# Peripherals.net
KiCad netlist of a schematic drawn in Altium Designer
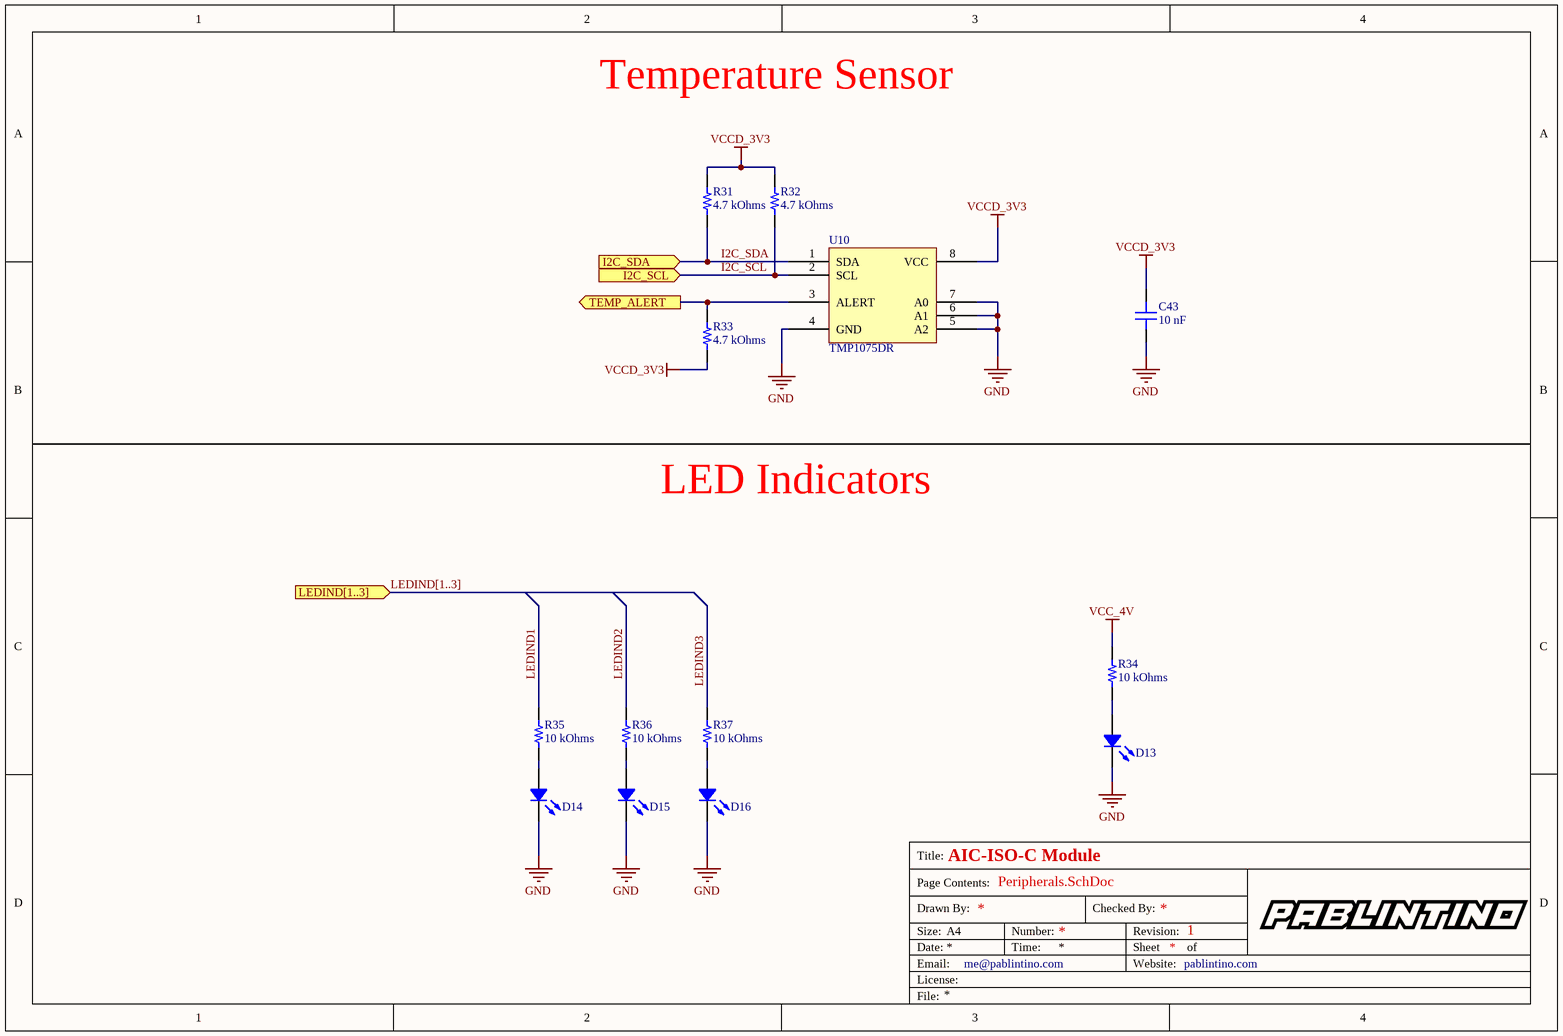
[diagram p0: Peripherals.SchDoc]

(export (version "E")
  (design (tool "Eeschema 10.0.6"))
  (components
    (comp (ref "C43")
      (value "10 nF")
      (footprint "CAP 0805_2012")
      (description "MLCC Ceramic 10 nF 50 V 10% Capacitor")
      (fields (field (name "PART NUMBER") "C0805C103K5GEC7210") (field (name "MANUFACTURER") "KEMET"))
      (libsource (lib "Database_Libs") (part "Capacitor"))
    )
    (comp (ref "D13")
      (value "APTD1608LSECK")
      (footprint "LED 0603_1608 RED")
      (description "SMD Low Current Red LED")
      (fields (field (name "MANUFACTURER") "Kingbright"))
      (libsource (lib "Database_Libs") (part "LED"))
    )
    (comp (ref "D14")
      (value "APTD1608LZGCK")
      (footprint "LED 0603_1608 GREEN")
      (description "SMD Low Current Green LED")
      (fields (field (name "MANUFACTURER") "Kingbright"))
      (libsource (lib "Database_Libs") (part "LED"))
    )
    (comp (ref "D15")
      (value "APTD1608LZGCK")
      (footprint "LED 0603_1608 GREEN")
      (description "SMD Low Current Green LED")
      (fields (field (name "MANUFACTURER") "Kingbright"))
      (libsource (lib "Database_Libs") (part "LED"))
    )
    (comp (ref "D16")
      (value "APTD1608LSECK")
      (footprint "LED 0603_1608 RED")
      (description "SMD Low Current Red LED")
      (fields (field (name "MANUFACTURER") "Kingbright"))
      (libsource (lib "Database_Libs") (part "LED"))
    )
    (comp (ref "R31")
      (value "4.7 kOhms")
      (footprint "RES 0603_1608")
      (description "Thin Film Resistor 4.7 kOhms 1%")
      (fields (field (name "PART NUMBER") "CRCW06034K70FKEAC") (field (name "MANUFACTURER") "Vishay / Dale"))
      (libsource (lib "Database_Libs") (part "Resistor"))
    )
    (comp (ref "R32")
      (value "4.7 kOhms")
      (footprint "RES 0603_1608")
      (description "Thin Film Resistor 4.7 kOhms 1%")
      (fields (field (name "PART NUMBER") "CRCW06034K70FKEAC") (field (name "MANUFACTURER") "Vishay / Dale"))
      (libsource (lib "Database_Libs") (part "Resistor"))
    )
    (comp (ref "R33")
      (value "4.7 kOhms")
      (footprint "RES 0603_1608")
      (description "Thin Film Resistor 4.7 kOhms 1%")
      (fields (field (name "PART NUMBER") "CRCW06034K70FKEAC") (field (name "MANUFACTURER") "Vishay / Dale"))
      (libsource (lib "Database_Libs") (part "Resistor"))
    )
    (comp (ref "R34")
      (value "10 kOhms")
      (footprint "RES 0603_1608")
      (description "Thin Film Resistor 10 kOhms 1%")
      (fields (field (name "PART NUMBER") "CRCW060310K0FKEAC") (field (name "MANUFACTURER") "Vishay / Dale"))
      (libsource (lib "Database_Libs") (part "Resistor"))
    )
    (comp (ref "R35")
      (value "10 kOhms")
      (footprint "RES 0603_1608")
      (description "Thin Film Resistor 10 kOhms 1%")
      (fields (field (name "PART NUMBER") "CRCW060310K0FKEAC") (field (name "MANUFACTURER") "Vishay / Dale"))
      (libsource (lib "Database_Libs") (part "Resistor"))
    )
    (comp (ref "R36")
      (value "10 kOhms")
      (footprint "RES 0603_1608")
      (description "Thin Film Resistor 10 kOhms 1%")
      (fields (field (name "PART NUMBER") "CRCW060310K0FKEAC") (field (name "MANUFACTURER") "Vishay / Dale"))
      (libsource (lib "Database_Libs") (part "Resistor"))
    )
    (comp (ref "R37")
      (value "10 kOhms")
      (footprint "RES 0603_1608")
      (description "Thin Film Resistor 10 kOhms 1%")
      (fields (field (name "PART NUMBER") "CRCW060310K0FKEAC") (field (name "MANUFACTURER") "Vishay / Dale"))
      (libsource (lib "Database_Libs") (part "Resistor"))
    )
    (comp (ref "U10")
      (value "TMP1075DR")
      (footprint "SOIC_DDAR_TEX")
      (description "TMP1075 Temperature Sensor With I2C and SMBus Interface")
      (libsource (lib "Database_Libs") (part "TMP1075"))
    )
  )
  (nets
    (net (code "1") (name "/I2C_SCL") (class "Default")
      (node (ref "R32") (pin "1") (pinfunction "1_1") (pintype "passive"))
      (node (ref "U10") (pin "2") (pinfunction "SCL_2") (pintype "passive"))
    )
    (net (code "2") (name "/I2C_SDA") (class "Default")
      (node (ref "R31") (pin "1") (pinfunction "1_1") (pintype "passive"))
      (node (ref "U10") (pin "1") (pinfunction "SDA_1") (pintype "passive"))
    )
    (net (code "3") (name "/LEDIND1") (class "Default")
      (node (ref "R35") (pin "1") (pinfunction "1_1") (pintype "passive"))
    )
    (net (code "4") (name "/LEDIND2") (class "Default")
      (node (ref "R36") (pin "1") (pinfunction "1_1") (pintype "passive"))
    )
    (net (code "5") (name "/LEDIND3") (class "Default")
      (node (ref "R37") (pin "1") (pinfunction "1_1") (pintype "passive"))
    )
    (net (code "7") (name "/TEMP_ALERT") (class "Default")
      (node (ref "R33") (pin "2") (pinfunction "2_2") (pintype "passive"))
      (node (ref "U10") (pin "3") (pinfunction "ALERT_3") (pintype "passive"))
    )
    (net (code "8") (name "GND") (class "Default")
      (node (ref "C43") (pin "2") (pinfunction "2_2") (pintype "passive"))
      (node (ref "D13") (pin "2") (pinfunction "2_2") (pintype "passive"))
      (node (ref "D14") (pin "2") (pinfunction "2_2") (pintype "passive"))
      (node (ref "D15") (pin "2") (pinfunction "2_2") (pintype "passive"))
      (node (ref "D16") (pin "2") (pinfunction "2_2") (pintype "passive"))
      (node (ref "U10") (pin "4") (pinfunction "GND_4") (pintype "passive"))
      (node (ref "U10") (pin "5") (pinfunction "A2_5") (pintype "passive"))
      (node (ref "U10") (pin "6") (pinfunction "A1_6") (pintype "passive"))
      (node (ref "U10") (pin "7") (pinfunction "A0_7") (pintype "passive"))
    )
    (net (code "9") (name "Net-(D13-Pad1)") (class "Default")
      (node (ref "D13") (pin "1") (pinfunction "1_1") (pintype "passive"))
      (node (ref "R34") (pin "2") (pinfunction "2_2") (pintype "passive"))
    )
    (net (code "10") (name "Net-(D14-Pad1)") (class "Default")
      (node (ref "D14") (pin "1") (pinfunction "1_1") (pintype "passive"))
      (node (ref "R35") (pin "2") (pinfunction "2_2") (pintype "passive"))
    )
    (net (code "11") (name "Net-(D15-Pad1)") (class "Default")
      (node (ref "D15") (pin "1") (pinfunction "1_1") (pintype "passive"))
      (node (ref "R36") (pin "2") (pinfunction "2_2") (pintype "passive"))
    )
    (net (code "12") (name "Net-(D16-Pad1)") (class "Default")
      (node (ref "D16") (pin "1") (pinfunction "1_1") (pintype "passive"))
      (node (ref "R37") (pin "2") (pinfunction "2_2") (pintype "passive"))
    )
    (net (code "13") (name "VCCD_3V3") (class "Default")
      (node (ref "C43") (pin "1") (pinfunction "1_1") (pintype "passive"))
      (node (ref "R31") (pin "2") (pinfunction "2_2") (pintype "passive"))
      (node (ref "R32") (pin "2") (pinfunction "2_2") (pintype "passive"))
      (node (ref "R33") (pin "1") (pinfunction "1_1") (pintype "passive"))
      (node (ref "U10") (pin "8") (pinfunction "VCC_8") (pintype "passive"))
    )
    (net (code "14") (name "VCC_4V") (class "Default")
      (node (ref "R34") (pin "1") (pinfunction "1_1") (pintype "passive"))
    )
  )
)
